# design.net
KiCad netlist of a schematic drawn in Altium Designer
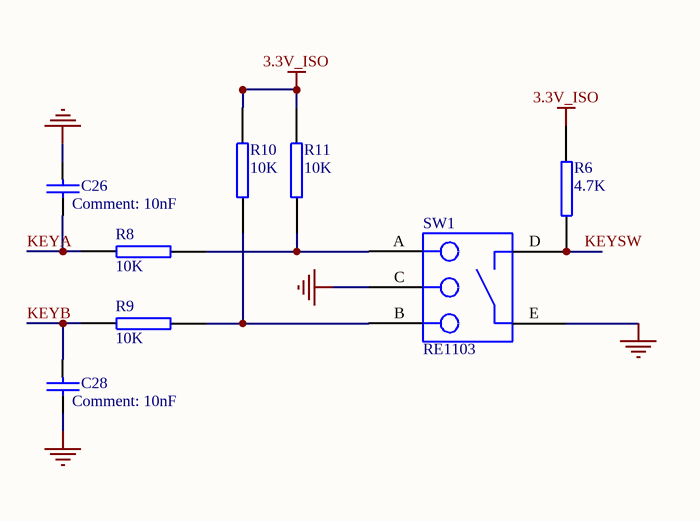
[diagram p0: 无极性旋钮.SchDoc]

(export (version "E")
  (design (tool "Eeschema 10.0.6"))
  (components
    (comp (ref "C26")
      (value "10nF")
      (footprint "0603C")
      (description "Capacitor")
      (libsource (lib "*") (part "CAP"))
    )
    (comp (ref "C28")
      (value "10nF")
      (footprint "0603C")
      (description "Capacitor")
      (libsource (lib "*") (part "CAP"))
    )
    (comp (ref "R6") (value "4.7K") (footprint "0603R") (libsource (lib "*") (part "RES2")))
    (comp (ref "R8") (value "10K") (footprint "0603R") (libsource (lib "*") (part "RES2")))
    (comp (ref "R9") (value "10K") (footprint "0603R") (libsource (lib "*") (part "RES2")))
    (comp (ref "R10") (value "10K") (footprint "0603R") (libsource (lib "*") (part "RES2")))
    (comp (ref "R11") (value "10K") (footprint "0603R") (libsource (lib "*") (part "RES2")))
    (comp (ref "SW1") (value "RE1103") (footprint "EX1103S-D2-10") (libsource (lib "*") (part "RE1103")))
  )
  (nets
    (net (code "1") (name "/KEYA") (class "Default")
      (node (ref "C26") (pin "2") (pinfunction "2_2") (pintype "passive"))
      (node (ref "R8") (pin "1") (pinfunction "1_1") (pintype "passive"))
    )
    (net (code "2") (name "/KEYB") (class "Default")
      (node (ref "C28") (pin "1") (pinfunction "1_1") (pintype "passive"))
      (node (ref "R9") (pin "1") (pinfunction "1_1") (pintype "passive"))
    )
    (net (code "3") (name "/KEYSW") (class "Default")
      (node (ref "R6") (pin "2") (pinfunction "2_2") (pintype "passive"))
      (node (ref "SW1") (pin "D") (pintype "passive"))
    )
    (net (code "4") (name "3.3V_ISO") (class "Default")
      (node (ref "R10") (pin "2") (pinfunction "2_2") (pintype "passive"))
      (node (ref "R11") (pin "2") (pinfunction "2_2") (pintype "passive"))
      (node (ref "R6") (pin "1") (pinfunction "1_1") (pintype "passive"))
    )
    (net (code "5") (name "GND") (class "Default")
      (node (ref "C26") (pin "1") (pinfunction "1_1") (pintype "passive"))
      (node (ref "C28") (pin "2") (pinfunction "2_2") (pintype "passive"))
      (node (ref "SW1") (pin "C") (pintype "passive"))
      (node (ref "SW1") (pin "E") (pintype "passive"))
    )
    (net (code "6") (name "Net-(R10-Pad1)") (class "Default")
      (node (ref "R10") (pin "1") (pinfunction "1_1") (pintype "passive"))
      (node (ref "R9") (pin "2") (pinfunction "2_2") (pintype "passive"))
      (node (ref "SW1") (pin "B") (pintype "passive"))
    )
    (net (code "7") (name "Net-(R11-Pad1)") (class "Default")
      (node (ref "R11") (pin "1") (pinfunction "1_1") (pintype "passive"))
      (node (ref "R8") (pin "2") (pinfunction "2_2") (pintype "passive"))
      (node (ref "SW1") (pin "A") (pintype "passive"))
    )
  )
)
